# LEDs.net
KiCad netlist of a schematic drawn in Altium Designer
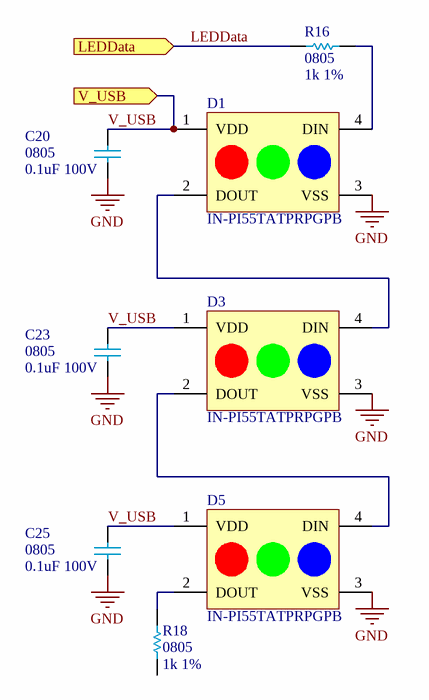
[diagram p0: LEDs.SchDoc]

(export (version "E")
  (design (tool "Eeschema 10.0.6"))
  (components
    (comp (ref "C20")
      (value "0805")
      (footprint "0805 - TALL")
      (description "0805, X5R or better")
      (fields (field (name "ALTIUM_VALUE") "0.1uF 100V"))
      (libsource (lib "Chip_Passives") (part "Cap 0.1uF 100V"))
    )
    (comp (ref "C23")
      (value "0805")
      (footprint "0805 - TALL")
      (description "0805, X5R or better")
      (fields (field (name "ALTIUM_VALUE") "0.1uF 100V"))
      (libsource (lib "Chip_Passives") (part "Cap 0.1uF 100V"))
    )
    (comp (ref "C25")
      (value "0805")
      (footprint "0805 - TALL")
      (description "0805, X5R or better")
      (fields (field (name "ALTIUM_VALUE") "0.1uF 100V"))
      (libsource (lib "Chip_Passives") (part "Cap 0.1uF 100V"))
    )
    (comp (ref "D1")
      (value "IN-PI55TATPRPGPB")
      (footprint "IN-PI55TATPRPGPB")
      (description "ADDRESS LED DISCRETE SERIAL RGB")
      (libsource (lib "LEDs") (part "IN-PI55TATPRPGPB"))
    )
    (comp (ref "D3")
      (value "IN-PI55TATPRPGPB")
      (footprint "IN-PI55TATPRPGPB")
      (description "ADDRESS LED DISCRETE SERIAL RGB")
      (libsource (lib "LEDs") (part "IN-PI55TATPRPGPB"))
    )
    (comp (ref "D5")
      (value "IN-PI55TATPRPGPB")
      (footprint "IN-PI55TATPRPGPB")
      (description "ADDRESS LED DISCRETE SERIAL RGB")
      (libsource (lib "LEDs") (part "IN-PI55TATPRPGPB"))
    )
    (comp (ref "R16")
      (value "0805")
      (footprint "0805")
      (description "Chip resistor, 1/8W 100PPM")
      (fields (field (name "ALTIUM_VALUE") "1k 1%"))
      (libsource (lib "Chip_Passives") (part "Res 1k 1% 0805"))
    )
    (comp (ref "R18")
      (value "0805")
      (footprint "0805")
      (description "Chip resistor, 1/8W 100PPM")
      (fields (field (name "ALTIUM_VALUE") "1k 1%"))
      (libsource (lib "Chip_Passives") (part "Res 1k 1% 0805"))
    )
  )
  (nets
    (net (code "1") (name "/LEDData") (class "Default")
      (node (ref "R16") (pin "2") (pinfunction "2_2") (pintype "passive"))
    )
    (net (code "2") (name "/V_USB") (class "Default")
      (node (ref "C20") (pin "2") (pinfunction "2_2") (pintype "passive"))
      (node (ref "C23") (pin "2") (pinfunction "2_2") (pintype "passive"))
      (node (ref "C25") (pin "2") (pinfunction "2_2") (pintype "passive"))
      (node (ref "D1") (pin "1") (pinfunction "VDD_1") (pintype "passive"))
      (node (ref "D3") (pin "1") (pinfunction "VDD_1") (pintype "passive"))
      (node (ref "D5") (pin "1") (pinfunction "VDD_1") (pintype "passive"))
    )
    (net (code "3") (name "GND") (class "Default")
      (node (ref "C20") (pin "1") (pinfunction "1_1") (pintype "passive"))
      (node (ref "C23") (pin "1") (pinfunction "1_1") (pintype "passive"))
      (node (ref "C25") (pin "1") (pinfunction "1_1") (pintype "passive"))
      (node (ref "D1") (pin "3") (pinfunction "VSS_3") (pintype "passive"))
      (node (ref "D3") (pin "3") (pinfunction "VSS_3") (pintype "passive"))
      (node (ref "D5") (pin "3") (pinfunction "VSS_3") (pintype "passive"))
    )
    (net (code "4") (name "Net-(D1-DIN)") (class "Default")
      (node (ref "D1") (pin "4") (pinfunction "DIN_4") (pintype "passive"))
      (node (ref "R16") (pin "1") (pinfunction "1_1") (pintype "passive"))
    )
    (net (code "5") (name "Net-(D1-DOUT)") (class "Default")
      (node (ref "D1") (pin "2") (pinfunction "DOUT_2") (pintype "passive"))
      (node (ref "D3") (pin "4") (pinfunction "DIN_4") (pintype "passive"))
    )
    (net (code "6") (name "Net-(D3-DOUT)") (class "Default")
      (node (ref "D3") (pin "2") (pinfunction "DOUT_2") (pintype "passive"))
      (node (ref "D5") (pin "4") (pinfunction "DIN_4") (pintype "passive"))
    )
    (net (code "7") (name "Net-(D5-DOUT)") (class "Default")
      (node (ref "D5") (pin "2") (pinfunction "DOUT_2") (pintype "passive"))
      (node (ref "R18") (pin "2") (pinfunction "2_2") (pintype "passive"))
    )
    (net (code "8") (name "unconnected-(R18-Pad1)") (class "Default")
      (node (ref "R18") (pin "1") (pinfunction "1_1") (pintype "passive"))
    )
  )
)
